# design.net
KiCad netlist of a schematic drawn in Altium Designer
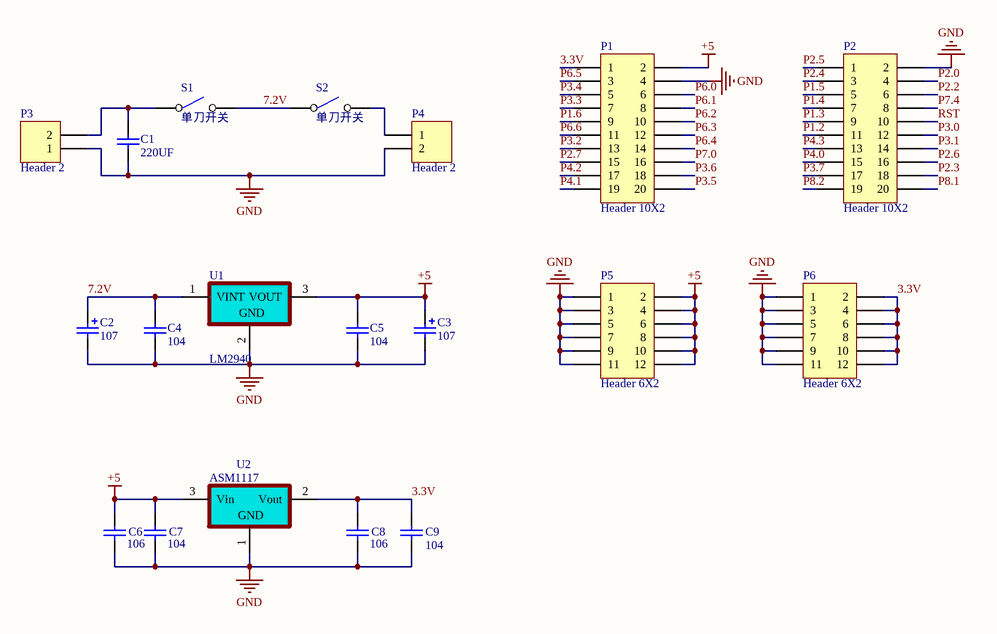
[diagram p0: 主板.SchDoc]

(export (version "E")
  (design (tool "Eeschema 10.0.6"))
  (components
    (comp (ref "C1")
      (value "220UF")
      (footprint "C-T电解F-330uF")
      (description "Capacitor")
      (fields (field (name "PUBLISHER") "Altium Limited"))
      (libsource (lib "Miscellaneous Devices") (part "Cap"))
    )
    (comp (ref "C2")
      (value "107")
      (footprint "107J/106E钽电容")
      (description "Polarized Capacitor (Axial)")
      (fields (field (name "PUBLISHER") "Altium Limited"))
      (libsource (lib "Miscellaneous Devices") (part "Cap Pol2"))
    )
    (comp (ref "C3")
      (value "107")
      (footprint "107J/106E钽电容")
      (description "Polarized Capacitor (Axial)")
      (fields (field (name "PUBLISHER") "Altium Limited"))
      (libsource (lib "Miscellaneous Devices") (part "Cap Pol2"))
    )
    (comp (ref "C4")
      (value "104")
      (footprint "0603AC")
      (description "Capacitor")
      (fields (field (name "PUBLISHER") "Altium Limited"))
      (libsource (lib "Miscellaneous Devices") (part "Cap"))
    )
    (comp (ref "C5")
      (value "104")
      (footprint "0603AC")
      (description "Capacitor")
      (fields (field (name "PUBLISHER") "Altium Limited"))
      (libsource (lib "Miscellaneous Devices") (part "Cap"))
    )
    (comp (ref "C6")
      (value "106")
      (footprint "0603AC")
      (description "Capacitor")
      (fields (field (name "PUBLISHER") "Altium Limited"))
      (libsource (lib "Miscellaneous Devices") (part "Cap"))
    )
    (comp (ref "C7")
      (value "104")
      (footprint "0603AC")
      (description "Capacitor")
      (fields (field (name "PUBLISHER") "Altium Limited"))
      (libsource (lib "Miscellaneous Devices") (part "Cap"))
    )
    (comp (ref "C8")
      (value "106")
      (footprint "0603AC")
      (description "Capacitor")
      (fields (field (name "PUBLISHER") "Altium Limited"))
      (libsource (lib "Miscellaneous Devices") (part "Cap"))
    )
    (comp (ref "C9")
      (value "104")
      (footprint "0603AC")
      (description "Capacitor")
      (fields (field (name "PUBLISHER") "Altium Limited"))
      (libsource (lib "Miscellaneous Devices") (part "Cap"))
    )
    (comp (ref "P1")
      (value "Header 10X2")
      (footprint "HDR2X10")
      (description "Header, 10-Pin, Dual row")
      (fields (field (name "PUBLISHER") "Altium Limited"))
      (libsource (lib "Miscellaneous Connectors") (part "Header 10X2"))
    )
    (comp (ref "P2")
      (value "Header 10X2")
      (footprint "HDR2X10")
      (description "Header, 10-Pin, Dual row")
      (fields (field (name "PUBLISHER") "Altium Limited"))
      (libsource (lib "Miscellaneous Connectors") (part "Header 10X2"))
    )
    (comp (ref "P3")
      (value "Header 2")
      (footprint "T型插")
      (description "Header, 2-Pin")
      (fields (field (name "PUBLISHER") "Altium Limited"))
      (libsource (lib "") (part "Header 2_1"))
    )
    (comp (ref "P4")
      (value "Header 2")
      (footprint "Con 2接线端子")
      (description "Header, 2-Pin")
      (fields (field (name "PUBLISHER") "Altium Limited"))
      (libsource (lib "Miscellaneous Connectors") (part "Header 2"))
    )
    (comp (ref "P5")
      (value "Header 6X2")
      (footprint "HDR2X6")
      (description "Header, 6-Pin, Dual row")
      (fields (field (name "PUBLISHER") "Altium Limited"))
      (libsource (lib "Miscellaneous Connectors") (part "Header 6X2"))
    )
    (comp (ref "P6")
      (value "Header 6X2")
      (footprint "HDR2X6")
      (description "Header, 6-Pin, Dual row")
      (fields (field (name "PUBLISHER") "Altium Limited"))
      (libsource (lib "Miscellaneous Connectors") (part "Header 6X2"))
    )
    (comp (ref "S1") (value "单刀开关") (footprint "船型开关（小2脚）") (libsource (lib "开关") (part "单刀开关")))
    (comp (ref "S2") (value "单刀开关") (footprint "船型开关（小2脚）") (libsource (lib "开关") (part "单刀开关")))
    (comp (ref "U1") (value "LM2940") (footprint "LM2940") (libsource (lib "*") (part "LM2940")))
    (comp (ref "U2")
      (value "ASM1117")
      (footprint "AMS1117")
      (description "ASM1117系列SOT-223封装稳压芯片")
      (libsource (lib "*") (part "ASM1117"))
    )
  )
  (nets
    (net (code "1") (name "+5") (class "Default")
      (node (ref "C3") (pin "1") (pinfunction "1_1") (pintype "passive"))
      (node (ref "C5") (pin "2") (pinfunction "2_2") (pintype "passive"))
      (node (ref "C6") (pin "2") (pinfunction "2_2") (pintype "passive"))
      (node (ref "C7") (pin "2") (pinfunction "2_2") (pintype "passive"))
      (node (ref "P1") (pin "2") (pinfunction "2_2") (pintype "passive"))
      (node (ref "P5") (pin "10") (pinfunction "10_10") (pintype "passive"))
      (node (ref "P5") (pin "12") (pinfunction "12_12") (pintype "passive"))
      (node (ref "P5") (pin "2") (pinfunction "2_2") (pintype "passive"))
      (node (ref "P5") (pin "4") (pinfunction "4_4") (pintype "passive"))
      (node (ref "P5") (pin "6") (pinfunction "6_6") (pintype "passive"))
      (node (ref "P5") (pin "8") (pinfunction "8_8") (pintype "passive"))
      (node (ref "U1") (pin "3") (pinfunction "VOUT_3") (pintype "passive"))
      (node (ref "U2") (pin "3") (pinfunction "Vin_3") (pintype "passive"))
    )
    (net (code "2") (name "/3.3V") (class "Default")
      (node (ref "C8") (pin "2") (pinfunction "2_2") (pintype "passive"))
      (node (ref "C9") (pin "2") (pinfunction "2_2") (pintype "passive"))
      (node (ref "P1") (pin "1") (pinfunction "1_1") (pintype "passive"))
      (node (ref "P6") (pin "10") (pinfunction "10_10") (pintype "passive"))
      (node (ref "P6") (pin "12") (pinfunction "12_12") (pintype "passive"))
      (node (ref "P6") (pin "2") (pinfunction "2_2") (pintype "passive"))
      (node (ref "P6") (pin "4") (pinfunction "4_4") (pintype "passive"))
      (node (ref "P6") (pin "6") (pinfunction "6_6") (pintype "passive"))
      (node (ref "P6") (pin "8") (pinfunction "8_8") (pintype "passive"))
      (node (ref "U2") (pin "2") (pinfunction "Vout_2") (pintype "passive"))
    )
    (net (code "3") (name "/7.2V") (class "Default")
      (node (ref "C2") (pin "1") (pinfunction "1_1") (pintype "passive"))
      (node (ref "C4") (pin "2") (pinfunction "2_2") (pintype "passive"))
      (node (ref "S1") (pin "2") (pinfunction "2_2") (pintype "passive"))
      (node (ref "S2") (pin "1") (pinfunction "1_1") (pintype "passive"))
      (node (ref "U1") (pin "1") (pinfunction "VINT_1") (pintype "passive"))
    )
    (net (code "4") (name "/P1.2") (class "Default")
      (node (ref "P2") (pin "11") (pinfunction "11_11") (pintype "passive"))
    )
    (net (code "5") (name "/P1.3") (class "Default")
      (node (ref "P2") (pin "9") (pinfunction "9_9") (pintype "passive"))
    )
    (net (code "6") (name "/P1.4") (class "Default")
      (node (ref "P2") (pin "7") (pinfunction "7_7") (pintype "passive"))
    )
    (net (code "7") (name "/P1.5") (class "Default")
      (node (ref "P2") (pin "5") (pinfunction "5_5") (pintype "passive"))
    )
    (net (code "8") (name "/P1.6") (class "Default")
      (node (ref "P1") (pin "9") (pinfunction "9_9") (pintype "passive"))
    )
    (net (code "9") (name "/P2.0") (class "Default")
      (node (ref "P2") (pin "4") (pinfunction "4_4") (pintype "passive"))
    )
    (net (code "10") (name "/P2.2") (class "Default")
      (node (ref "P2") (pin "6") (pinfunction "6_6") (pintype "passive"))
    )
    (net (code "11") (name "/P2.3") (class "Default")
      (node (ref "P2") (pin "18") (pinfunction "18_18") (pintype "passive"))
    )
    (net (code "12") (name "/P2.4") (class "Default")
      (node (ref "P2") (pin "3") (pinfunction "3_3") (pintype "passive"))
    )
    (net (code "13") (name "/P2.5") (class "Default")
      (node (ref "P2") (pin "1") (pinfunction "1_1") (pintype "passive"))
    )
    (net (code "14") (name "/P2.6") (class "Default")
      (node (ref "P2") (pin "16") (pinfunction "16_16") (pintype "passive"))
    )
    (net (code "15") (name "/P2.7") (class "Default")
      (node (ref "P1") (pin "15") (pinfunction "15_15") (pintype "passive"))
    )
    (net (code "16") (name "/P3.0") (class "Default")
      (node (ref "P2") (pin "12") (pinfunction "12_12") (pintype "passive"))
    )
    (net (code "17") (name "/P3.1") (class "Default")
      (node (ref "P2") (pin "14") (pinfunction "14_14") (pintype "passive"))
    )
    (net (code "18") (name "/P3.2") (class "Default")
      (node (ref "P1") (pin "13") (pinfunction "13_13") (pintype "passive"))
    )
    (net (code "19") (name "/P3.3") (class "Default")
      (node (ref "P1") (pin "7") (pinfunction "7_7") (pintype "passive"))
    )
    (net (code "20") (name "/P3.4") (class "Default")
      (node (ref "P1") (pin "5") (pinfunction "5_5") (pintype "passive"))
    )
    (net (code "21") (name "/P3.5") (class "Default")
      (node (ref "P1") (pin "20") (pinfunction "20_20") (pintype "passive"))
    )
    (net (code "22") (name "/P3.6") (class "Default")
      (node (ref "P1") (pin "18") (pinfunction "18_18") (pintype "passive"))
    )
    (net (code "23") (name "/P3.7") (class "Default")
      (node (ref "P2") (pin "17") (pinfunction "17_17") (pintype "passive"))
    )
    (net (code "24") (name "/P4.0") (class "Default")
      (node (ref "P2") (pin "15") (pinfunction "15_15") (pintype "passive"))
    )
    (net (code "25") (name "/P4.1") (class "Default")
      (node (ref "P1") (pin "19") (pinfunction "19_19") (pintype "passive"))
    )
    (net (code "26") (name "/P4.2") (class "Default")
      (node (ref "P1") (pin "17") (pinfunction "17_17") (pintype "passive"))
    )
    (net (code "27") (name "/P4.3") (class "Default")
      (node (ref "P2") (pin "13") (pinfunction "13_13") (pintype "passive"))
    )
    (net (code "28") (name "/P6.0") (class "Default")
      (node (ref "P1") (pin "6") (pinfunction "6_6") (pintype "passive"))
    )
    (net (code "29") (name "/P6.1") (class "Default")
      (node (ref "P1") (pin "8") (pinfunction "8_8") (pintype "passive"))
    )
    (net (code "30") (name "/P6.2") (class "Default")
      (node (ref "P1") (pin "10") (pinfunction "10_10") (pintype "passive"))
    )
    (net (code "31") (name "/P6.3") (class "Default")
      (node (ref "P1") (pin "12") (pinfunction "12_12") (pintype "passive"))
    )
    (net (code "32") (name "/P6.4") (class "Default")
      (node (ref "P1") (pin "14") (pinfunction "14_14") (pintype "passive"))
    )
    (net (code "33") (name "/P6.5") (class "Default")
      (node (ref "P1") (pin "3") (pinfunction "3_3") (pintype "passive"))
    )
    (net (code "34") (name "/P6.6") (class "Default")
      (node (ref "P1") (pin "11") (pinfunction "11_11") (pintype "passive"))
    )
    (net (code "35") (name "/P7.0") (class "Default")
      (node (ref "P1") (pin "16") (pinfunction "16_16") (pintype "passive"))
    )
    (net (code "36") (name "/P7.4") (class "Default")
      (node (ref "P2") (pin "8") (pinfunction "8_8") (pintype "passive"))
    )
    (net (code "37") (name "/P8.1") (class "Default")
      (node (ref "P2") (pin "20") (pinfunction "20_20") (pintype "passive"))
    )
    (net (code "38") (name "/P8.2") (class "Default")
      (node (ref "P2") (pin "19") (pinfunction "19_19") (pintype "passive"))
    )
    (net (code "39") (name "/RST") (class "Default")
      (node (ref "P2") (pin "10") (pinfunction "10_10") (pintype "passive"))
    )
    (net (code "40") (name "GND") (class "Default")
      (node (ref "C1") (pin "2") (pinfunction "2_2") (pintype "passive"))
      (node (ref "C2") (pin "2") (pinfunction "2_2") (pintype "passive"))
      (node (ref "C3") (pin "2") (pinfunction "2_2") (pintype "passive"))
      (node (ref "C4") (pin "1") (pinfunction "1_1") (pintype "passive"))
      (node (ref "C5") (pin "1") (pinfunction "1_1") (pintype "passive"))
      (node (ref "C6") (pin "1") (pinfunction "1_1") (pintype "passive"))
      (node (ref "C7") (pin "1") (pinfunction "1_1") (pintype "passive"))
      (node (ref "C8") (pin "1") (pinfunction "1_1") (pintype "passive"))
      (node (ref "C9") (pin "1") (pinfunction "1_1") (pintype "passive"))
      (node (ref "P1") (pin "4") (pinfunction "4_4") (pintype "passive"))
      (node (ref "P2") (pin "2") (pinfunction "2_2") (pintype "passive"))
      (node (ref "P3") (pin "1") (pinfunction "1_1") (pintype "passive"))
      (node (ref "P4") (pin "2") (pinfunction "2_2") (pintype "passive"))
      (node (ref "P5") (pin "1") (pinfunction "1_1") (pintype "passive"))
      (node (ref "P5") (pin "11") (pinfunction "11_11") (pintype "passive"))
      (node (ref "P5") (pin "3") (pinfunction "3_3") (pintype "passive"))
      (node (ref "P5") (pin "5") (pinfunction "5_5") (pintype "passive"))
      (node (ref "P5") (pin "7") (pinfunction "7_7") (pintype "passive"))
      (node (ref "P5") (pin "9") (pinfunction "9_9") (pintype "passive"))
      (node (ref "P6") (pin "1") (pinfunction "1_1") (pintype "passive"))
      (node (ref "P6") (pin "11") (pinfunction "11_11") (pintype "passive"))
      (node (ref "P6") (pin "3") (pinfunction "3_3") (pintype "passive"))
      (node (ref "P6") (pin "5") (pinfunction "5_5") (pintype "passive"))
      (node (ref "P6") (pin "7") (pinfunction "7_7") (pintype "passive"))
      (node (ref "P6") (pin "9") (pinfunction "9_9") (pintype "passive"))
      (node (ref "U1") (pin "2") (pinfunction "GND_2") (pintype "passive"))
      (node (ref "U2") (pin "1") (pinfunction "Gnd_1") (pintype "passive"))
    )
    (net (code "41") (name "Net-(C1-Pad1)") (class "Default")
      (node (ref "C1") (pin "1") (pinfunction "1_1") (pintype "passive"))
      (node (ref "P3") (pin "2") (pinfunction "2_2") (pintype "passive"))
      (node (ref "S1") (pin "1") (pinfunction "1_1") (pintype "passive"))
    )
    (net (code "42") (name "Net-(P4-Pad1)") (class "Default")
      (node (ref "P4") (pin "1") (pinfunction "1_1") (pintype "passive"))
      (node (ref "S2") (pin "2") (pinfunction "2_2") (pintype "passive"))
    )
  )
)
